# OpAmpSCH.net
KiCad netlist of a schematic drawn in Altium Designer
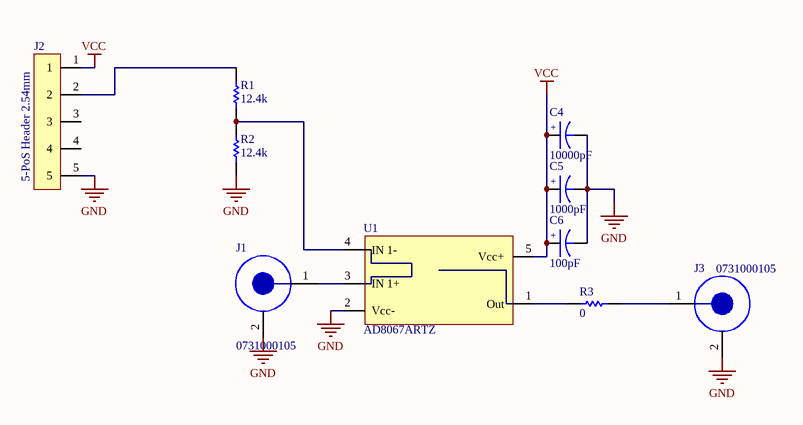
[diagram p0: OpAmpSCH.SchDoc]

(export (version "E")
  (design (tool "Eeschema 10.0.6"))
  (components
    (comp (ref "C4")
      (value "10000pF")
      (footprint "0603C")
      (description "Cap Poly")
      (libsource (lib "GENERIC_LIB") (part "CPoly"))
    )
    (comp (ref "C5")
      (value "1000pF")
      (footprint "0603C")
      (description "Cap Poly")
      (libsource (lib "GENERIC_LIB") (part "CPoly"))
    )
    (comp (ref "C6")
      (value "100pF")
      (footprint "0603C")
      (description "Cap Poly")
      (libsource (lib "GENERIC_LIB") (part "CPoly"))
    )
    (comp (ref "J1")
      (value "0731000105")
      (footprint "0731000105")
      (description "BNC Connector Jack, Female Socket 50Ohm Through Hole, Right Angle Solder")
      (libsource (lib "CON_LIB") (part "0731000105"))
    )
    (comp (ref "J2")
      (value "5-PoS Header 2.54mm")
      (footprint "2.54mm Pitch Header")
      (libsource (lib "CON_LIB") (part "5-PoS Header 2.54mm"))
    )
    (comp (ref "J3")
      (value "0731000105")
      (footprint "0731000105")
      (description "BNC Connector Jack, Female Socket 50Ohm Through Hole, Right Angle Solder")
      (libsource (lib "CON_LIB") (part "0731000105"))
    )
    (comp (ref "R1")
      (value "12.4k")
      (footprint "0603C")
      (description "Resistor")
      (fields (field (name "TOLERANCE") "5%"))
      (libsource (lib "GENERIC_LIB") (part "R"))
    )
    (comp (ref "R2")
      (value "12.4k")
      (footprint "0603C")
      (description "Resistor")
      (fields (field (name "TOLERANCE") "5%"))
      (libsource (lib "GENERIC_LIB") (part "R"))
    )
    (comp (ref "R3")
      (value "0")
      (footprint "1206C")
      (description "Resistor")
      (fields (field (name "TOLERANCE") "5%"))
      (libsource (lib "GENERIC_LIB") (part "R"))
    )
    (comp (ref "U1")
      (value "AD8067ARTZ")
      (footprint "MIC920")
      (description "IC OPAMP VFB 1")
      (libsource (lib "ANALOG_LIB") (part "AD8067ARTZ"))
    )
  )
  (nets
    (net (code "1") (name "GND") (class "Default")
      (node (ref "C4") (pin "2") (pinfunction "2_2") (pintype "passive"))
      (node (ref "C5") (pin "2") (pinfunction "2_2") (pintype "passive"))
      (node (ref "C6") (pin "2") (pinfunction "2_2") (pintype "passive"))
      (node (ref "J1") (pin "2") (pinfunction "2_2") (pintype "passive"))
      (node (ref "J2") (pin "5") (pinfunction "5_5") (pintype "passive"))
      (node (ref "J3") (pin "2") (pinfunction "2_2") (pintype "passive"))
      (node (ref "R2") (pin "1") (pinfunction "1_1") (pintype "passive"))
      (node (ref "U1") (pin "2") (pinfunction "Vcc-_2") (pintype "passive"))
    )
    (net (code "2") (name "Net-(J2-Pad2)") (class "Default")
      (node (ref "J2") (pin "2") (pinfunction "2_2") (pintype "passive"))
      (node (ref "R1") (pin "2") (pinfunction "2_2") (pintype "passive"))
    )
    (net (code "3") (name "Net-(J3-Pad1)") (class "Default")
      (node (ref "J3") (pin "1") (pinfunction "1_1") (pintype "passive"))
      (node (ref "R3") (pin "2") (pinfunction "2_2") (pintype "passive"))
    )
    (net (code "4") (name "Net-(U1-IN_1+)") (class "Default")
      (node (ref "J1") (pin "1") (pinfunction "1_1") (pintype "passive"))
      (node (ref "U1") (pin "3") (pinfunction "IN_1+_3") (pintype "passive"))
    )
    (net (code "5") (name "Net-(U1-IN_1-)") (class "Default")
      (node (ref "R1") (pin "1") (pinfunction "1_1") (pintype "passive"))
      (node (ref "R2") (pin "2") (pinfunction "2_2") (pintype "passive"))
      (node (ref "U1") (pin "4") (pinfunction "IN_1-_4") (pintype "passive"))
    )
    (net (code "6") (name "Net-(U1-Out)") (class "Default")
      (node (ref "R3") (pin "1") (pinfunction "1_1") (pintype "passive"))
      (node (ref "U1") (pin "1") (pinfunction "Out_1") (pintype "passive"))
    )
    (net (code "7") (name "VCC") (class "Default")
      (node (ref "C4") (pin "1") (pinfunction "1_1") (pintype "passive"))
      (node (ref "C5") (pin "1") (pinfunction "1_1") (pintype "passive"))
      (node (ref "C6") (pin "1") (pinfunction "1_1") (pintype "passive"))
      (node (ref "J2") (pin "1") (pinfunction "1_1") (pintype "passive"))
      (node (ref "U1") (pin "5") (pinfunction "Vcc+_5") (pintype "passive"))
    )
    (net (code "8") (name "unconnected-(J2-Pad3)") (class "Default")
      (node (ref "J2") (pin "3") (pinfunction "3_3") (pintype "passive"))
    )
    (net (code "9") (name "unconnected-(J2-Pad4)") (class "Default")
      (node (ref "J2") (pin "4") (pinfunction "4_4") (pintype "passive"))
    )
  )
)
